# SiLPA_RF_detector.net
KiCad netlist of a schematic drawn in Altium Designer
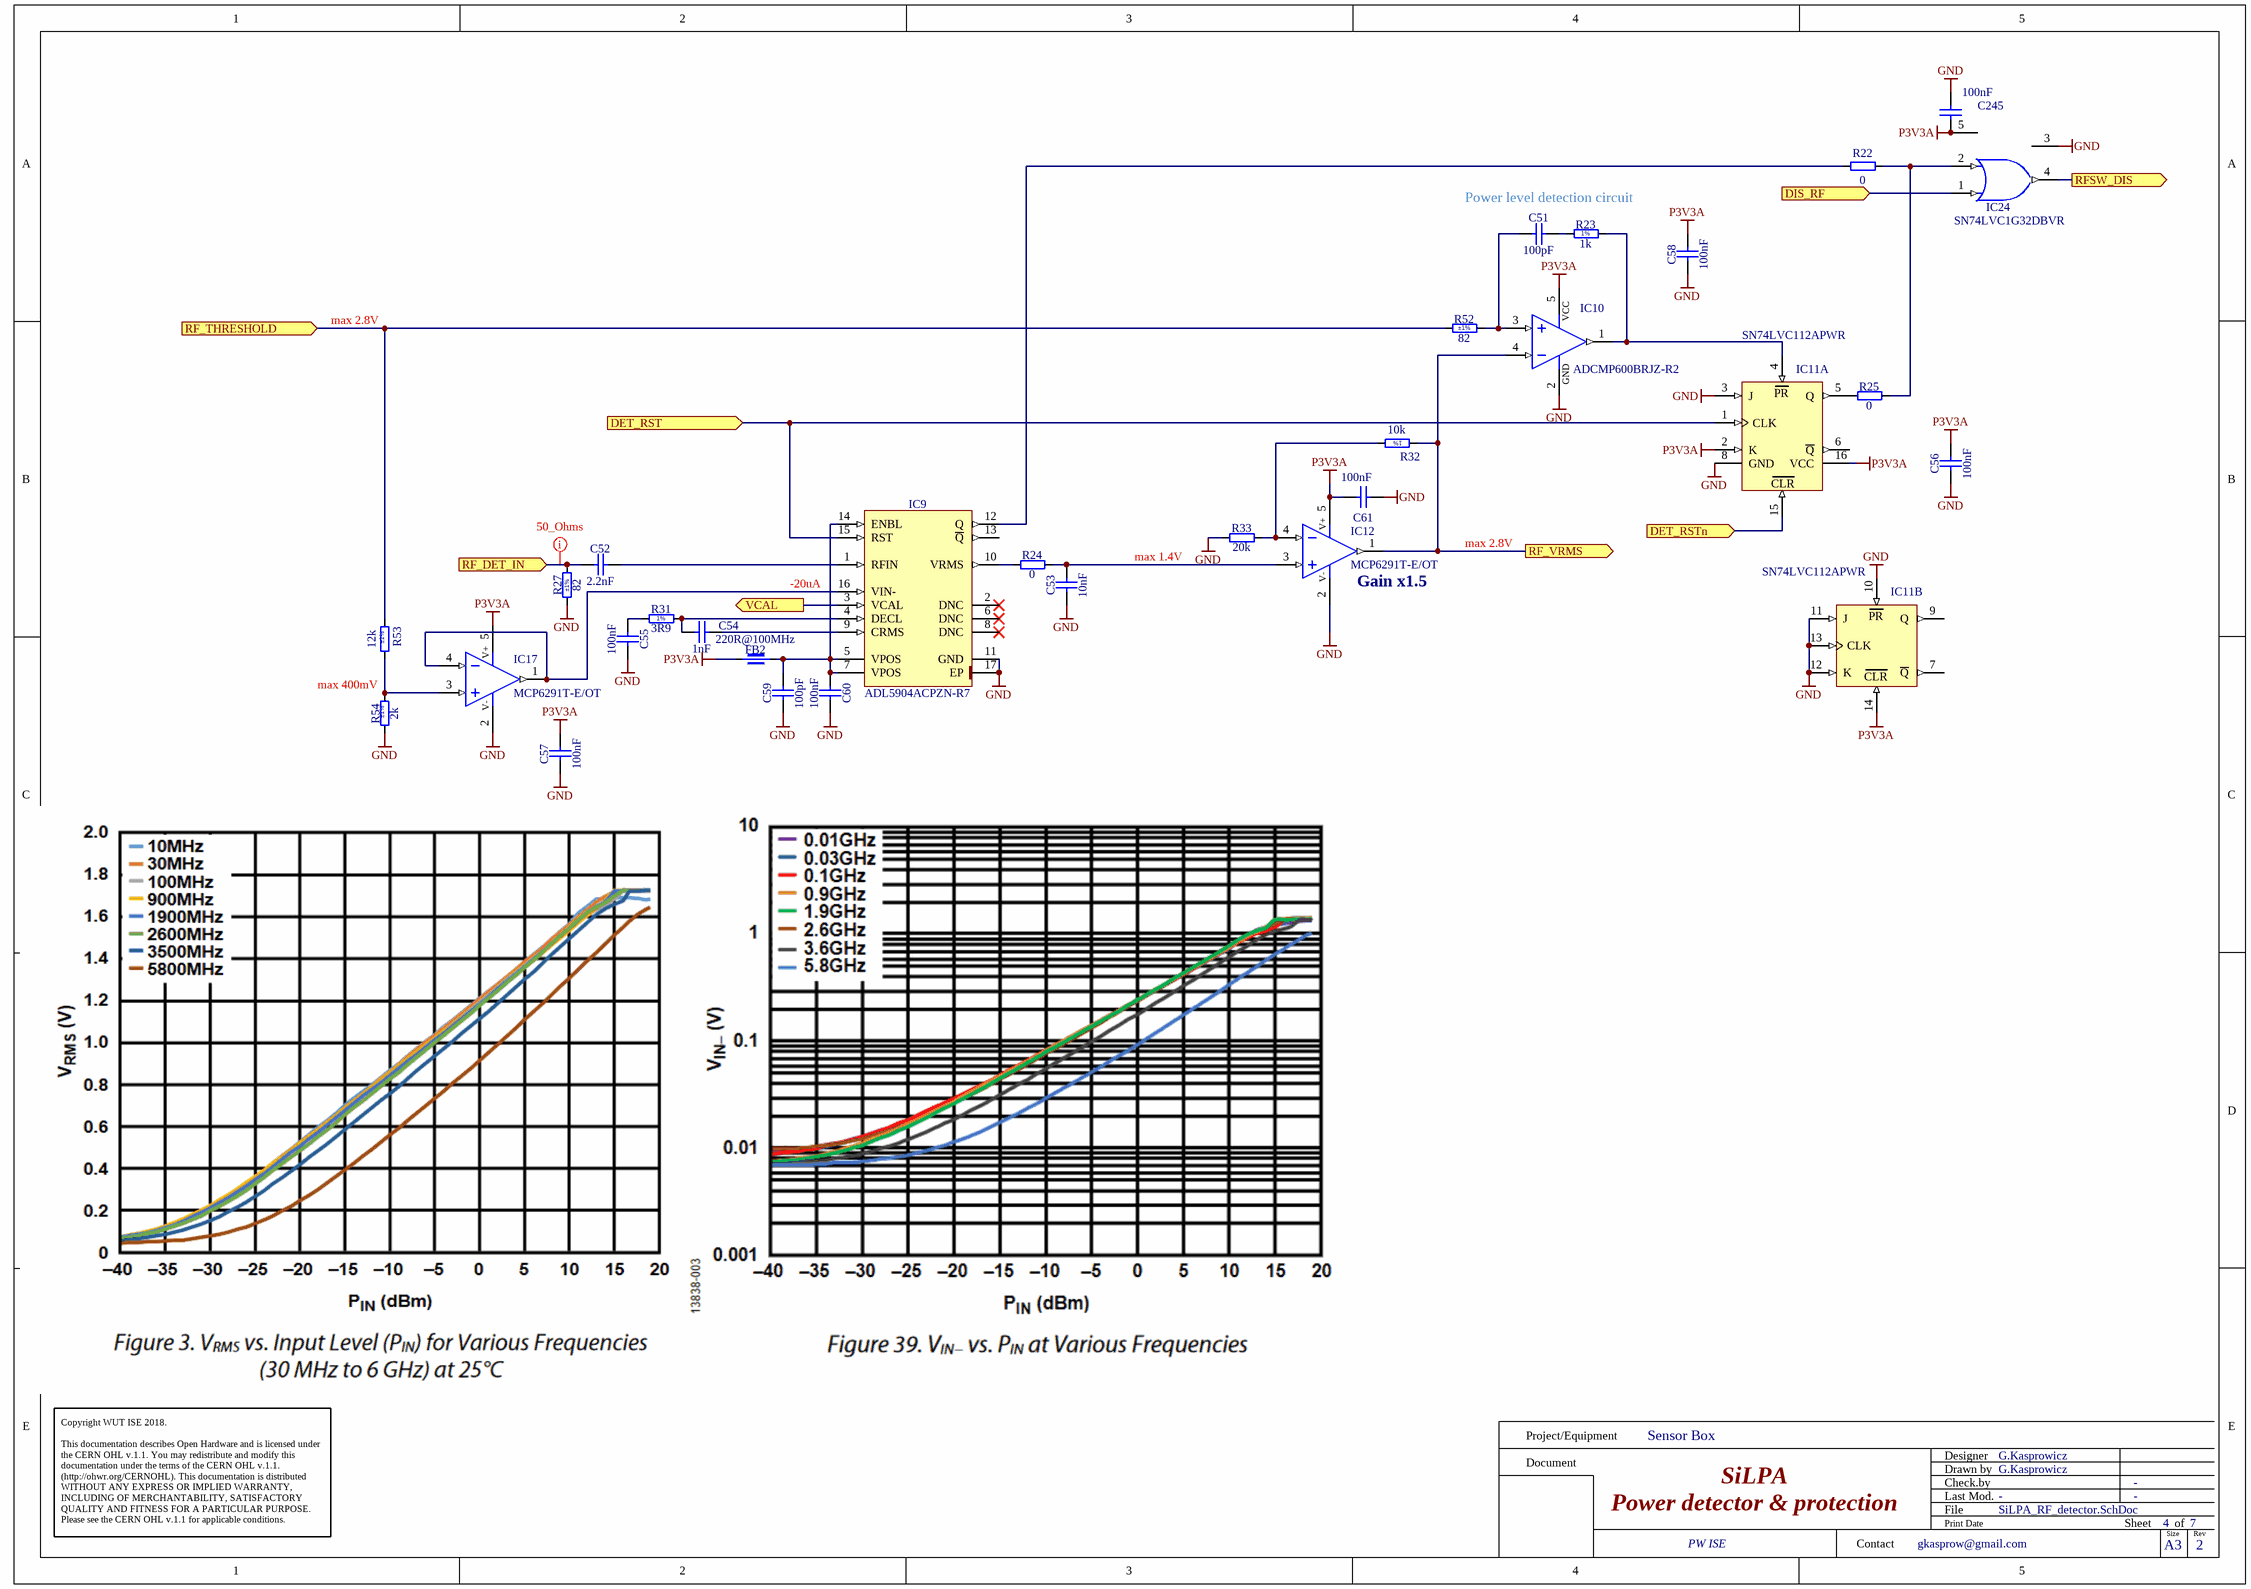
[diagram p0: SiLPA_RF_detector.SchDoc]

(export (version "E")
  (design (tool "Eeschema 10.0.6"))
  (components
    (comp (ref "C51")
      (value "100pF")
      (footprint "CAPC1005X55N")
      (description "Non-polarised capacitor")
      (fields
        (field (name "PART NUMBER") "CC0402_100PF_50V_5%_C0G")
        (field (name "VOLTAGE") "50V")
        (field (name "AUTHOR") "CERN DEM JLC")
      )
      (libsource (lib "Capacitors") (part "Capacitor - non polarized"))
    )
    (comp (ref "C52")
      (value "2.2nF")
      (footprint "CAPC1608X87N")
      (description "Non-polarised capacitor")
      (fields
        (field (name "MANUFACTURER") "GENERIC")
        (field (name "MANUFACTURER PART NUMBER") "CC0603_2.2NF_50V_5%_C0G")
        (field (name "AUTHOR") "CERN DEM JMW")
      )
      (libsource (lib "Capacitors") (part "Capacitor - non polarized"))
    )
    (comp (ref "C53")
      (value "10nF")
      (footprint "CAPC1005X55N")
      (description "Non-polarised capacitor")
      (fields
        (field (name "MANUFACTURER") "GENERIC")
        (field (name "MANUFACTURER PART NUMBER") "CC0402_10NF_25V_10%_X7R")
        (field (name "AUTHOR") "CERN DEM JLC")
      )
      (libsource (lib "Capacitors") (part "Capacitor - non polarized"))
    )
    (comp (ref "C54")
      (value "1nF")
      (footprint "CAPC1005X55N")
      (description "Non-polarised capacitor")
      (fields
        (field (name "PART NUMBER") "CC0402_1NF_50V_10%_X7R")
        (field (name "VOLTAGE") "50V")
        (field (name "AUTHOR") "CERN DEM JLC")
      )
      (libsource (lib "Capacitors") (part "Capacitor - non polarized"))
    )
    (comp (ref "C55")
      (value "100nF")
      (footprint "CAPC1005X55N")
      (description "Non-polarised capacitor")
      (fields
        (field (name "MANUFACTURER") "GENERIC")
        (field (name "MANUFACTURER PART NUMBER") "CC0402_100NF_50V_10%_X7R")
        (field (name "AUTHOR") "CERN DEM MR")
      )
      (libsource (lib "Capacitors") (part "Capacitor - non polarized"))
    )
    (comp (ref "C56")
      (value "100nF")
      (footprint "CAPC1005X55N")
      (description "Non-polarised capacitor")
      (fields
        (field (name "PART NUMBER") "CC0402_100NF_16V_10%_X5R")
        (field (name "VOLTAGE") "16V")
        (field (name "AUTHOR") "CERN DEM JLC")
      )
      (libsource (lib "Capacitors") (part "Capacitor - non polarized"))
    )
    (comp (ref "C57")
      (value "100nF")
      (footprint "CAPC1005X55N")
      (description "Non-polarised capacitor")
      (fields
        (field (name "PART NUMBER") "CC0402_100NF_16V_10%_X5R")
        (field (name "VOLTAGE") "16V")
        (field (name "AUTHOR") "CERN DEM JLC")
      )
      (libsource (lib "Capacitors") (part "Capacitor - non polarized"))
    )
    (comp (ref "C58")
      (value "100nF")
      (footprint "CAPC1005X55N")
      (description "Non-polarised capacitor")
      (fields
        (field (name "PART NUMBER") "CC0402_100NF_16V_10%_X5R")
        (field (name "VOLTAGE") "16V")
        (field (name "AUTHOR") "CERN DEM JLC")
      )
      (libsource (lib "Capacitors") (part "Capacitor - non polarized"))
    )
    (comp (ref "C59")
      (value "100pF")
      (footprint "CAPC1005X55N")
      (description "Non-polarised capacitor")
      (fields
        (field (name "PART NUMBER") "CC0402_100PF_50V_5%_C0G")
        (field (name "VOLTAGE") "50V")
        (field (name "AUTHOR") "CERN DEM JLC")
      )
      (libsource (lib "Capacitors") (part "Capacitor - non polarized"))
    )
    (comp (ref "C60")
      (value "100nF")
      (footprint "CAPC1005X55N")
      (description "Non-polarised capacitor")
      (fields
        (field (name "MANUFACTURER") "GENERIC")
        (field (name "MANUFACTURER PART NUMBER") "CC0402_100NF_50V_10%_X7R")
        (field (name "AUTHOR") "CERN DEM MR")
      )
      (libsource (lib "Capacitors") (part "Capacitor - non polarized"))
    )
    (comp (ref "C61")
      (value "100nF")
      (footprint "CAPC1005X55N")
      (description "Non-polarised capacitor")
      (fields
        (field (name "MANUFACTURER") "GENERIC")
        (field (name "MANUFACTURER PART NUMBER") "CC0402_100NF_16V_10%_X5R")
        (field (name "AUTHOR") "CERN DEM JLC")
      )
      (libsource (lib "Capacitors") (part "Capacitor - non polarized"))
    )
    (comp (ref "C245")
      (value "100nF")
      (footprint "CAPC1005X55N")
      (description "Non-polarised capacitor")
      (fields
        (field (name "PART NUMBER") "CC0402_100NF_16V_10%_X5R")
        (field (name "VOLTAGE") "16V")
        (field (name "AUTHOR") "CERN DEM JLC")
      )
      (libsource (lib "Capacitors") (part "Capacitor - non polarized"))
    )
    (comp (ref "FB2")
      (value "220R@100MHz")
      (footprint "INDC1005X55N")
      (fields
        (field (name "PART NUMBER") "IND0402_MURATA_BLM15HB221SN1")
        (field (name "POWER") "250mA")
        (field (name "TOLERANCE") "±25%")
        (field (name "AUTHOR") "CERN DEM JLC")
      )
      (libsource (lib "Inductors & Transformers") (part "Ferrite Bead"))
    )
    (comp (ref "IC9")
      (value "ADL5904ACPZN-R7")
      (footprint "QFN50P300X300X80-17N-S175")
      (description "DC to 6 GHz, 45 dB TruPwr Detector With Envelope Threshold Detection")
      (fields (field (name "MANUFACTURER") "ANALOG DEVICES") (field (name "AUTHOR") "CERN DEM MR"))
      (libsource (lib "ICs And Semiconductors") (part "ADL5904"))
    )
    (comp (ref "IC10")
      (value "ADCMP600BRJZ-R2")
      (footprint "SOT95P280X145-5N")
      (description "Rail-to-Rail, Very Fast, 2.5 V to 5.5 V Single-Supply TTL/CMOS Comparator")
      (fields (field (name "MANUFACTURER") "ANALOG DEVICES") (field (name "AUTHOR") "CERN DEM JLC"))
      (libsource (lib "ICs And Semiconductors") (part "ADCMP600"))
    )
    (comp (ref "IC11")
      (value "SN74LVC112APWR")
      (footprint "SOP65P640X120-16N")
      (description "Dual Negative-Edge-Triggered J-K Flip-Flop With Clear And Preset")
      (fields (field (name "MANUFACTURER") "TEXAS INSTRUMENTS") (field (name "AUTHOR") "CERN DEM JLC"))
      (libsource (lib "ICS-logic") (part "74LVC112APWR"))
    )
    (comp (ref "IC12")
      (value "MCP6291T-E/OT")
      (footprint "SOT95P270X145-5N")
      (description "Operational Amplifier")
      (fields (field (name "MANUFACTURER") "MICROCHIP TECHNOLOGY") (field (name "AUTHOR") "CERN DEM BC"))
      (libsource (lib "ICs And Semiconductors") (part "Operational Amplifier Type7"))
    )
    (comp (ref "IC17")
      (value "MCP6291T-E/OT")
      (footprint "SOT95P270X145-5N")
      (description "Operational Amplifier")
      (fields (field (name "MANUFACTURER") "MICROCHIP TECHNOLOGY") (field (name "AUTHOR") "CERN DEM BC"))
      (libsource (lib "ICs And Semiconductors") (part "Operational Amplifier Type7"))
    )
    (comp (ref "IC24")
      (value "SN74LVC1G32DBVR")
      (footprint "SOT95P280X145-5N")
      (description "Single 2-Input Positive-OR Gate")
      (fields (field (name "MANUFACTURER") "TEXAS INSTRUMENTS") (field (name "AUTHOR") "CERN DEM JLC"))
      (libsource (lib "ICs And Semiconductors") (part "741G32"))
    )
    (comp (ref "R22")
      (value "0")
      (footprint "RESC1608X55N")
      (description "Resistor")
      (fields
        (field (name "PART NUMBER") "R0603_0R_JUMPER")
        (field (name "MANUFACTURER") "GENERIC")
        (field (name "AUTHOR") "CERN DEM JLC")
      )
      (libsource (lib "Resistors") (part "Resistor"))
    )
    (comp (ref "R23")
      (value "1k")
      (footprint "RESC1005X40N")
      (description "Resistor - 1%")
      (fields
        (field (name "PART NUMBER") "R0402_1K_1%_0.0625W_100PPM")
        (field (name "POWER") "0.0625W")
        (field (name "AUTHOR") "CERN DEM JLC")
      )
      (libsource (lib "Resistors") (part "Resistor - 1%"))
    )
    (comp (ref "R24")
      (value "0")
      (footprint "RESC1005X40N")
      (description "Resistor")
      (fields
        (field (name "MANUFACTURER") "GENERIC")
        (field (name "MANUFACTURER PART NUMBER") "R0402_0R_JUMPER")
        (field (name "AUTHOR") "CERN DEM JLC")
      )
      (libsource (lib "Resistors") (part "Resistor"))
    )
    (comp (ref "R25")
      (value "0")
      (footprint "RESC1608X55N")
      (description "Resistor")
      (fields
        (field (name "PART NUMBER") "R0603_0R_JUMPER")
        (field (name "MANUFACTURER") "GENERIC")
        (field (name "AUTHOR") "CERN DEM JLC")
      )
      (libsource (lib "Resistors") (part "Resistor"))
    )
    (comp (ref "R27")
      (value "82")
      (footprint "RESC1608X55N")
      (description "Resistor - 1%")
      (fields
        (field (name "TOLERANCE") "±1%")
        (field (name "PART NUMBER") "R0603_82R_1%_0.1W_100PPM")
        (field (name "POWER") "0.1W")
        (field (name "AUTHOR") "CERN DEM JLC")
      )
      (libsource (lib "") (part "Resistor - 1%_1"))
    )
    (comp (ref "R31")
      (value "3R9")
      (footprint "RESC1005X40N")
      (description "Resistor - 1%")
      (fields
        (field (name "PART NUMBER") "R0402_3R9_1%_0.0625W_200PPM")
        (field (name "POWER") "0.0625W")
        (field (name "AUTHOR") "CERN DEM JLC")
      )
      (libsource (lib "Resistors") (part "Resistor - 1%"))
    )
    (comp (ref "R32")
      (value "10k")
      (footprint "RESC1005X40N")
      (description "Resistor - 1%")
      (fields
        (field (name "MANUFACTURER") "GENERIC")
        (field (name "MANUFACTURER PART NUMBER") "R0402_10K_1%_0.0625W_100PPM")
        (field (name "AUTHOR") "CERN DEM JLC")
      )
      (libsource (lib "Resistors") (part "Resistor - 1%"))
    )
    (comp (ref "R33")
      (value "20k")
      (footprint "RESC1005X40N")
      (description "Resistor - 1%")
      (fields
        (field (name "PART NUMBER") "R0402_20K_1%_0.0625W_100PPM")
        (field (name "POWER") "0.0625W")
        (field (name "AUTHOR") "CERN DEM JLC")
      )
      (libsource (lib "Resistors") (part "Resistor - 1%"))
    )
    (comp (ref "R52")
      (value "82")
      (footprint "RESC1005X40N")
      (description "Resistor - 1%")
      (fields
        (field (name "TOLERANCE") "±1%")
        (field (name "PART NUMBER") "R0402_82R_1%_0.0625W_100PPM")
        (field (name "POWER") "0.0625W")
        (field (name "AUTHOR") "CERN DEM JLC")
      )
      (libsource (lib "Resistors") (part "Resistor - 1%"))
    )
    (comp (ref "R53")
      (value "12k")
      (footprint "RESC1005X40N")
      (description "Resistor - 1%")
      (fields
        (field (name "MANUFACTURER") "GENERIC")
        (field (name "MANUFACTURER PART NUMBER") "R0402_12K_1%_0.0625W_100PPM")
        (field (name "TOLERANCE") "±1%")
        (field (name "AUTHOR") "CERN DEM JLC")
      )
      (libsource (lib "Resistors") (part "Resistor - 1%"))
    )
    (comp (ref "R54")
      (value "2k")
      (footprint "RESC1005X40N")
      (description "Resistor - 1%")
      (fields
        (field (name "PART NUMBER") "R0402_2K_1%_0.0625W_100PPM")
        (field (name "POWER") "0.0625W")
        (field (name "TOLERANCE") "±1%")
        (field (name "AUTHOR") "CERN DEM JLC")
      )
      (libsource (lib "Resistors") (part "Resistor - 1%"))
    )
  )
  (nets
    (net (code "1") (name "/DET_RST") (class "Default")
      (node (ref "IC11") (pin "1") (pinfunction "CLK_1") (pintype "input"))
      (node (ref "IC9") (pin "15") (pinfunction "RST_15") (pintype "input"))
    )
    (net (code "2") (name "/DET_RSTn") (class "Default")
      (node (ref "IC11") (pin "15") (pinfunction "~{CLR}_15") (pintype "input"))
    )
    (net (code "3") (name "/DIS_RF") (class "Default")
      (node (ref "IC24") (pin "1") (pinfunction "A_1") (pintype "input"))
    )
    (net (code "4") (name "/RFSW_DIS") (class "Default")
      (node (ref "IC24") (pin "4") (pinfunction "Y_4") (pintype "output"))
    )
    (net (code "5") (name "/RF_DET_IN") (class "Default")
      (node (ref "C52") (pin "1") (pinfunction "1_1") (pintype "passive"))
      (node (ref "R27") (pin "2") (pinfunction "2_2") (pintype "passive"))
    )
    (net (code "6") (name "/RF_THRESHOLD") (class "Default")
      (node (ref "R52") (pin "1") (pinfunction "1_1") (pintype "passive"))
      (node (ref "R53") (pin "1") (pinfunction "1_1") (pintype "passive"))
    )
    (net (code "7") (name "/RF_VRMS") (class "Default")
      (node (ref "IC10") (pin "4") (pinfunction "VN_4") (pintype "input"))
      (node (ref "IC12") (pin "1") (pinfunction "OUT_1") (pintype "output"))
      (node (ref "R32") (pin "1") (pinfunction "1_1") (pintype "passive"))
    )
    (net (code "8") (name "/VCAL") (class "Default")
      (node (ref "IC9") (pin "3") (pinfunction "VCAL_3") (pintype "input"))
    )
    (net (code "9") (name "GND") (class "Default")
      (node (ref "C245") (pin "2") (pinfunction "2_2") (pintype "passive"))
      (node (ref "C53") (pin "1") (pinfunction "1_1") (pintype "passive"))
      (node (ref "C55") (pin "2") (pinfunction "2_2") (pintype "passive"))
      (node (ref "C56") (pin "1") (pinfunction "1_1") (pintype "passive"))
      (node (ref "C57") (pin "1") (pinfunction "1_1") (pintype "passive"))
      (node (ref "C58") (pin "1") (pinfunction "1_1") (pintype "passive"))
      (node (ref "C59") (pin "1") (pinfunction "1_1") (pintype "passive"))
      (node (ref "C60") (pin "2") (pinfunction "2_2") (pintype "passive"))
      (node (ref "C61") (pin "1") (pinfunction "1_1") (pintype "passive"))
      (node (ref "IC10") (pin "2") (pinfunction "GND_2") (pintype "power_in"))
      (node (ref "IC11") (pin "10") (pinfunction "~{PRE}_10") (pintype "input"))
      (node (ref "IC11") (pin "11") (pinfunction "J_11") (pintype "input"))
      (node (ref "IC11") (pin "12") (pinfunction "K_12") (pintype "input"))
      (node (ref "IC11") (pin "13") (pinfunction "CLK_13") (pintype "input"))
      (node (ref "IC11") (pin "3") (pinfunction "J_3") (pintype "input"))
      (node (ref "IC11") (pin "8") (pinfunction "GND_8") (pintype "power_in"))
      (node (ref "IC12") (pin "2") (pinfunction "V-_2") (pintype "power_in"))
      (node (ref "IC17") (pin "2") (pinfunction "V-_2") (pintype "power_in"))
      (node (ref "IC24") (pin "3") (pinfunction "GND_3") (pintype "power_in"))
      (node (ref "IC9") (pin "11") (pinfunction "GND_11") (pintype "power_in"))
      (node (ref "IC9") (pin "17") (pinfunction "EP_17") (pintype "power_in"))
      (node (ref "R27") (pin "1") (pinfunction "1_1") (pintype "passive"))
      (node (ref "R33") (pin "1") (pinfunction "1_1") (pintype "passive"))
      (node (ref "R54") (pin "1") (pinfunction "1_1") (pintype "passive"))
    )
    (net (code "10") (name "Net-(C51-Pad2)") (class "Default")
      (node (ref "C51") (pin "2") (pinfunction "2_2") (pintype "passive"))
      (node (ref "R23") (pin "1") (pinfunction "1_1") (pintype "passive"))
    )
    (net (code "11") (name "Net-(C55-Pad1)") (class "Default")
      (node (ref "C55") (pin "1") (pinfunction "1_1") (pintype "passive"))
      (node (ref "R31") (pin "1") (pinfunction "1_1") (pintype "passive"))
    )
    (net (code "12") (name "Net-(IC9-CRMS)") (class "Default")
      (node (ref "C54") (pin "2") (pinfunction "2_2") (pintype "passive"))
      (node (ref "IC9") (pin "9") (pinfunction "CRMS_9") (pintype "input"))
    )
    (net (code "13") (name "Net-(IC9-DECL)") (class "Default")
      (node (ref "C54") (pin "1") (pinfunction "1_1") (pintype "passive"))
      (node (ref "IC9") (pin "4") (pinfunction "DECL_4") (pintype "input"))
      (node (ref "R31") (pin "2") (pinfunction "2_2") (pintype "passive"))
    )
    (net (code "14") (name "Net-(IC9-ENBL)") (class "Default")
      (node (ref "C59") (pin "2") (pinfunction "2_2") (pintype "passive"))
      (node (ref "C60") (pin "1") (pinfunction "1_1") (pintype "passive"))
      (node (ref "FB2") (pin "2") (pinfunction "2_2") (pintype "passive"))
      (node (ref "IC9") (pin "14") (pinfunction "ENBL_14") (pintype "input"))
      (node (ref "IC9") (pin "5") (pinfunction "VPOS_5") (pintype "power_in"))
      (node (ref "IC9") (pin "7") (pinfunction "VPOS_7") (pintype "power_in"))
    )
    (net (code "15") (name "Net-(IC9-Q)") (class "Default")
      (node (ref "IC9") (pin "12") (pinfunction "Q_12") (pintype "output"))
      (node (ref "R22") (pin "1") (pinfunction "1_1") (pintype "passive"))
    )
    (net (code "16") (name "Net-(IC9-RFIN)") (class "Default")
      (node (ref "C52") (pin "2") (pinfunction "2_2") (pintype "passive"))
      (node (ref "IC9") (pin "1") (pinfunction "RFIN_1") (pintype "input"))
    )
    (net (code "17") (name "Net-(IC9-VRMS)") (class "Default")
      (node (ref "IC9") (pin "10") (pinfunction "VRMS_10") (pintype "output"))
      (node (ref "R24") (pin "1") (pinfunction "1_1") (pintype "passive"))
    )
    (net (code "18") (name "Net-(IC10-VP)") (class "Default")
      (node (ref "C51") (pin "1") (pinfunction "1_1") (pintype "passive"))
      (node (ref "IC10") (pin "3") (pinfunction "VP_3") (pintype "input"))
      (node (ref "R52") (pin "2") (pinfunction "2_2") (pintype "passive"))
    )
    (net (code "19") (name "Net-(IC10-q)") (class "Default")
      (node (ref "IC10") (pin "1") (pinfunction "q_1") (pintype "output"))
      (node (ref "IC11") (pin "4") (pinfunction "~{PRE}_4") (pintype "input"))
      (node (ref "R23") (pin "2") (pinfunction "2_2") (pintype "passive"))
    )
    (net (code "20") (name "Net-(IC11A-Q)") (class "Default")
      (node (ref "IC11") (pin "5") (pinfunction "Q_5") (pintype "output"))
      (node (ref "R25") (pin "1") (pinfunction "1_1") (pintype "passive"))
    )
    (net (code "21") (name "Net-(IC12-IN+)") (class "Default")
      (node (ref "C53") (pin "2") (pinfunction "2_2") (pintype "passive"))
      (node (ref "IC12") (pin "3") (pinfunction "IN+_3") (pintype "input"))
      (node (ref "R24") (pin "2") (pinfunction "2_2") (pintype "passive"))
    )
    (net (code "22") (name "Net-(IC12-IN-)") (class "Default")
      (node (ref "IC12") (pin "4") (pinfunction "IN-_4") (pintype "input"))
      (node (ref "R32") (pin "2") (pinfunction "2_2") (pintype "passive"))
      (node (ref "R33") (pin "2") (pinfunction "2_2") (pintype "passive"))
    )
    (net (code "23") (name "Net-(IC17-IN+)") (class "Default")
      (node (ref "IC17") (pin "3") (pinfunction "IN+_3") (pintype "input"))
      (node (ref "R53") (pin "2") (pinfunction "2_2") (pintype "passive"))
      (node (ref "R54") (pin "2") (pinfunction "2_2") (pintype "passive"))
    )
    (net (code "24") (name "Net-(IC17-IN-)") (class "Default")
      (node (ref "IC17") (pin "1") (pinfunction "OUT_1") (pintype "output"))
      (node (ref "IC17") (pin "4") (pinfunction "IN-_4") (pintype "input"))
      (node (ref "IC9") (pin "16") (pinfunction "VIN-_16") (pintype "input"))
    )
    (net (code "25") (name "Net-(IC24-B)") (class "Default")
      (node (ref "IC24") (pin "2") (pinfunction "B_2") (pintype "input"))
      (node (ref "R22") (pin "2") (pinfunction "2_2") (pintype "passive"))
      (node (ref "R25") (pin "2") (pinfunction "2_2") (pintype "passive"))
    )
    (net (code "26") (name "P3V3A") (class "Default")
      (node (ref "C245") (pin "1") (pinfunction "1_1") (pintype "passive"))
      (node (ref "C56") (pin "2") (pinfunction "2_2") (pintype "passive"))
      (node (ref "C57") (pin "2") (pinfunction "2_2") (pintype "passive"))
      (node (ref "C58") (pin "2") (pinfunction "2_2") (pintype "passive"))
      (node (ref "C61") (pin "2") (pinfunction "2_2") (pintype "passive"))
      (node (ref "FB2") (pin "1") (pinfunction "1_1") (pintype "passive"))
      (node (ref "IC10") (pin "5") (pinfunction "VCC_5") (pintype "power_in"))
      (node (ref "IC11") (pin "14") (pinfunction "~{CLR}_14") (pintype "input"))
      (node (ref "IC11") (pin "16") (pinfunction "VCC_16") (pintype "power_in"))
      (node (ref "IC11") (pin "2") (pinfunction "K_2") (pintype "input"))
      (node (ref "IC12") (pin "5") (pinfunction "V+_5") (pintype "power_in"))
      (node (ref "IC17") (pin "5") (pinfunction "V+_5") (pintype "power_in"))
      (node (ref "IC24") (pin "5") (pinfunction "VCC_5") (pintype "power_in"))
    )
    (net (code "27") (name "unconnected-(IC9-DNC-Pad2)") (class "Default")
      (node (ref "IC9") (pin "2") (pinfunction "DNC_2") (pintype "passive+no_connect"))
    )
    (net (code "28") (name "unconnected-(IC9-DNC-Pad6)") (class "Default")
      (node (ref "IC9") (pin "6") (pinfunction "DNC_6") (pintype "passive+no_connect"))
    )
    (net (code "29") (name "unconnected-(IC9-DNC-Pad8)") (class "Default")
      (node (ref "IC9") (pin "8") (pinfunction "DNC_8") (pintype "passive+no_connect"))
    )
    (net (code "30") (name "unconnected-(IC9-~{Q}-Pad13)") (class "Default")
      (node (ref "IC9") (pin "13") (pinfunction "~{Q}_13") (pintype "output"))
    )
    (net (code "31") (name "unconnected-(IC11A-~{Q}-Pad6)") (class "Default")
      (node (ref "IC11") (pin "6") (pinfunction "~{Q}_6") (pintype "output"))
    )
    (net (code "32") (name "unconnected-(IC11B-Q-Pad9)") (class "Default")
      (node (ref "IC11") (pin "9") (pinfunction "Q_9") (pintype "output"))
    )
    (net (code "33") (name "unconnected-(IC11B-~{Q}-Pad7)") (class "Default")
      (node (ref "IC11") (pin "7") (pinfunction "~{Q}_7") (pintype "output"))
    )
  )
)
